# Copy_of_pilpal_final.net
KiCad netlist of a schematic drawn in Altium Designer
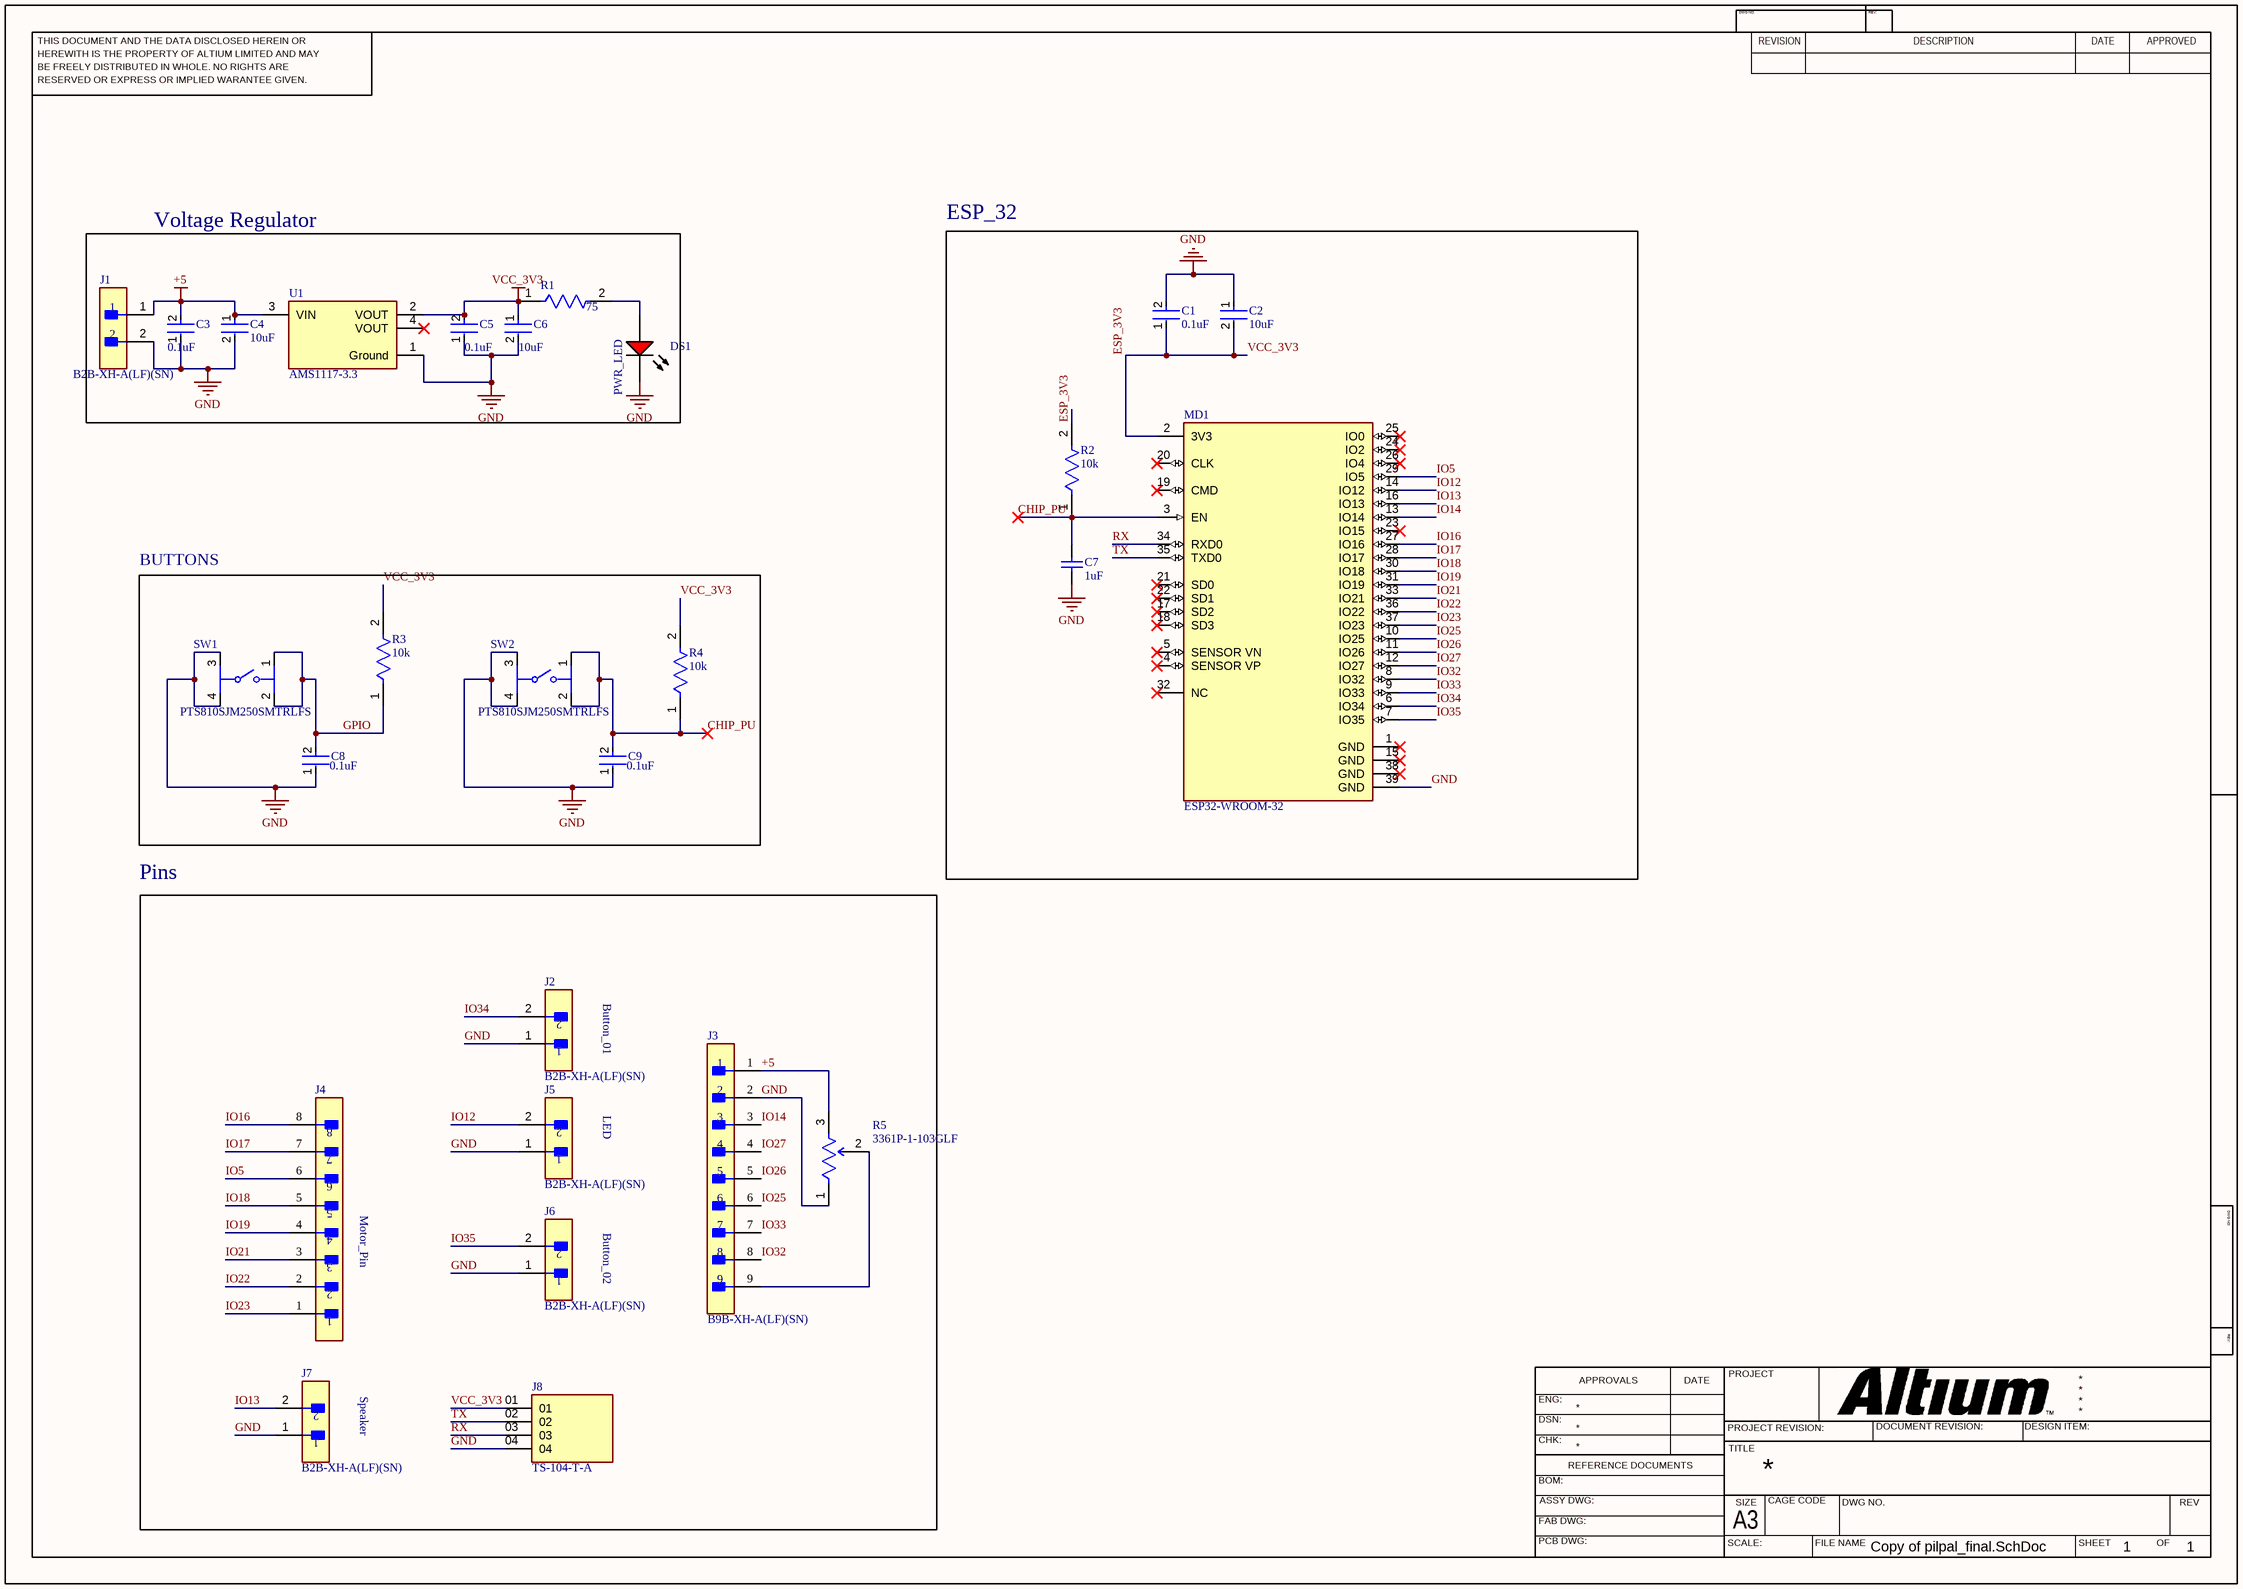
[diagram p0: Copy of pilpal_final.SchDoc]

(export (version "E")
  (design (tool "Eeschema 10.0.6"))
  (components
    (comp (ref "C1")
      (value "0.1uF")
      (footprint "FP-GRM15-MFG")
      (description "CAP CER 0.1UF 16V X7R 0402")
      (fields (field (name "MANUFACTURER PART NUMBER") "GRM155R71C104KA88D") (field (name "TOLERANCE") "10%"))
      (libsource (lib "Altium Content Vault") (part "236180d848d6139a670b325ea6854c9"))
    )
    (comp (ref "C2")
      (value "10uF")
      (footprint "FP-GRM188-0_1-e0_2_0_55-IPC_A")
      (description "Chip Multilayer Ceramic Capacitors for General Purpose, 0603, 10uF, X5R, 15%, 20%, 6.3V")
      (fields (field (name "VOLTAGE") "6.3V") (field (name "TOLERANCE") "20%"))
      (libsource (lib "Altium Content Vault") (part "02cd4be3c70576c341d710602a673aa"))
    )
    (comp (ref "C3")
      (value "0.1uF")
      (footprint "FP-GRM15-MFG")
      (description "CAP CER 0.1UF 16V X7R 0402")
      (fields (field (name "MANUFACTURER PART NUMBER") "GRM155R71C104KA88D") (field (name "TOLERANCE") "10%"))
      (libsource (lib "Altium Content Vault") (part "236180d848d6139a670b325ea6854c9"))
    )
    (comp (ref "C4")
      (value "10uF")
      (footprint "FP-GRM188-0_1-e0_2_0_55-IPC_A")
      (description "Chip Multilayer Ceramic Capacitors for General Purpose, 0603, 10uF, X5R, 15%, 20%, 6.3V")
      (fields (field (name "VOLTAGE") "6.3V") (field (name "TOLERANCE") "20%"))
      (libsource (lib "Altium Content Vault") (part "02cd4be3c70576c341d710602a673aa"))
    )
    (comp (ref "C5")
      (value "0.1uF")
      (footprint "FP-GRM15-MFG")
      (description "CAP CER 0.1UF 16V X7R 0402")
      (fields (field (name "MANUFACTURER PART NUMBER") "GRM155R71C104KA88D") (field (name "TOLERANCE") "10%"))
      (libsource (lib "Altium Content Vault") (part "236180d848d6139a670b325ea6854c9"))
    )
    (comp (ref "C6")
      (value "10uF")
      (footprint "FP-GRM188-0_1-e0_2_0_55-IPC_A")
      (description "Chip Multilayer Ceramic Capacitors for General Purpose, 0603, 10uF, X5R, 15%, 20%, 6.3V")
      (fields (field (name "VOLTAGE") "6.3V") (field (name "TOLERANCE") "20%"))
      (libsource (lib "Altium Content Vault") (part "02cd4be3c70576c341d710602a673aa"))
    )
    (comp (ref "C7")
      (value "1uF")
      (footprint "CAPC2013X145X50ML20T25")
      (fields (field (name "PART NUMBER") "C0805C105K9PACTU") (field (name "MANUFACTURER") "Kemet"))
      (libsource (lib "Altium Content Vault") (part "CAP"))
    )
    (comp (ref "C8")
      (value "0.1uF")
      (footprint "FP-GRM15-MFG")
      (description "CAP CER 0.1UF 16V X7R 0402")
      (fields (field (name "MANUFACTURER PART NUMBER") "GRM155R71C104KA88D") (field (name "TOLERANCE") "10%"))
      (libsource (lib "Altium Content Vault") (part "236180d848d6139a670b325ea6854c9"))
    )
    (comp (ref "C9")
      (value "0.1uF")
      (footprint "FP-GRM15-MFG")
      (description "CAP CER 0.1UF 16V X7R 0402")
      (fields (field (name "MANUFACTURER PART NUMBER") "GRM155R71C104KA88D") (field (name "TOLERANCE") "10%"))
      (libsource (lib "Altium Content Vault") (part "236180d848d6139a670b325ea6854c9"))
    )
    (comp (ref "DS1")
      (value "PWR_LED")
      (footprint "AVAG-HSMX-C150_V")
      (description "LED Uni-Color Red, 65 mW, 25 mA, -40 to 85 degC, 2-Pin SMD, RoHS, Tape and Reel")
      (fields (field (name "MANUFACTURER") "Avago"))
      (libsource (lib "Altium Content Vault") (part "LED-RED-AK-2"))
    )
    (comp (ref "J1")
      (value "B2B-XH-A(LF)(SN)")
      (footprint "FP-B2B-XH-A_LF_SN-MFG")
      (description "CONN HEADER VERT 2POS 2.5MM")
      (libsource (lib "") (part "3bc925449376181038e59eaffc5286c_1"))
    )
    (comp (ref "J2")
      (value "B2B-XH-A(LF)(SN)")
      (footprint "FP-B2B-XH-A_LF_SN-MFG")
      (description "CONN HEADER VERT 2POS 2.5MM")
      (libsource (lib "Altium Content Vault") (part "3bc925449376181038e59eaffc5286c"))
    )
    (comp (ref "J3")
      (value "B9B-XH-A(LF)(SN)")
      (footprint "FP-B9B-XH-A_LF_SN-MFG")
      (description "CONN HEADER VERT 9POS 2.5MM")
      (libsource (lib "Altium Content Vault") (part "dac6df820644cf490af5575b4ac23d9"))
    )
    (comp (ref "J4")
      (value "B8B-XH-A(LF)(SN)")
      (footprint "FP-B8B-XH-A_LF_SN-MFG")
      (description "CONN HEADER VERT 8POS 2.5MM")
      (libsource (lib "Altium Content Vault") (part "99ec2b232beb5d2356d4d77f6a047f0"))
    )
    (comp (ref "J5")
      (value "B2B-XH-A(LF)(SN)")
      (footprint "FP-B2B-XH-A_LF_SN-MFG")
      (description "CONN HEADER VERT 2POS 2.5MM")
      (libsource (lib "Altium Content Vault") (part "3bc925449376181038e59eaffc5286c"))
    )
    (comp (ref "J6")
      (value "B2B-XH-A(LF)(SN)")
      (footprint "FP-B2B-XH-A_LF_SN-MFG")
      (description "CONN HEADER VERT 2POS 2.5MM")
      (libsource (lib "Altium Content Vault") (part "3bc925449376181038e59eaffc5286c"))
    )
    (comp (ref "J7")
      (value "B2B-XH-A(LF)(SN)")
      (footprint "FP-B2B-XH-A_LF_SN-MFG")
      (description "CONN HEADER VERT 2POS 2.5MM")
      (libsource (lib "Altium Content Vault") (part "3bc925449376181038e59eaffc5286c"))
    )
    (comp (ref "J8")
      (value "TS-104-T-A")
      (footprint "SAMTEC_TS-104-T-A")
      (description "TS - Samtec 2.54mm Single Row Machined Terminal Strip - Fast Stock")
      (fields (field (name "MF") "Samtec Inc."))
      (libsource (lib "TS-104-T-A") (part "TS-104-T-A"))
    )
    (comp (ref "MD1")
      (value "ESP32-WROOM-32")
      (footprint "FP-ESP32-WROOM-32-MFG")
      (description "RX TXRX MOD WIFI SURFACE MOUNT")
      (libsource (lib "Altium Content Vault") (part "ee866abf0b6c51247b7f5cdebf2f250"))
    )
    (comp (ref "R1")
      (value "75")
      (footprint "FP-RN731J-MFG")
      (description "Thin Film Resistors RN 0603 750Ω 0.1% 10ppm/°C")
      (fields (field (name "TOLERANCE") "0.1%") (field (name "MANUFACTURER") "TE Connectivity"))
      (libsource (lib "Altium Content Vault") (part "1029c3af85768c4190bb7ad29bc67b5"))
    )
    (comp (ref "R2")
      (value "10k")
      (footprint "FP-CRG0805-IPC_C")
      (description "RES SMD 10K OHM 1% 1/8W 0805")
      (fields (field (name "TOLERANCE") "1%"))
      (libsource (lib "Altium Content Vault") (part "1029c3af85768c4190bb7ad29bc67b5"))
    )
    (comp (ref "R3")
      (value "10k")
      (footprint "FP-CRG0805-IPC_C")
      (description "RES SMD 10K OHM 1% 1/8W 0805")
      (fields (field (name "TOLERANCE") "1%"))
      (libsource (lib "Altium Content Vault") (part "1029c3af85768c4190bb7ad29bc67b5"))
    )
    (comp (ref "R4")
      (value "10k")
      (footprint "FP-CRG0805-IPC_C")
      (description "RES SMD 10K OHM 1% 1/8W 0805")
      (fields (field (name "TOLERANCE") "1%"))
      (libsource (lib "Altium Content Vault") (part "1029c3af85768c4190bb7ad29bc67b5"))
    )
    (comp (ref "R5")
      (value "3361P-1-103GLF")
      (footprint "FP-3361P-MFG")
      (description "TRIMMER 10K OHM 0.5W GW TOP ADJ")
      (fields (field (name "TOLERANCE") "10%"))
      (libsource (lib "Altium Content Vault") (part "2dcfd2547301a7d3209a5e99acfd772"))
    )
    (comp (ref "SW1")
      (value "PTS810SJM250SMTRLFS")
      (footprint "FP-PTS810SJM250SMTRLFS-MFG")
      (description "SWITCH TACTILE SPST-NO 0.05A 16V")
      (libsource (lib "Altium Content Vault") (part "1adf0dd01260c80cf25a44bfd6b99ba"))
    )
    (comp (ref "SW2")
      (value "PTS810SJM250SMTRLFS")
      (footprint "FP-PTS810SJM250SMTRLFS-MFG")
      (description "SWITCH TACTILE SPST-NO 0.05A 16V")
      (libsource (lib "Altium Content Vault") (part "1adf0dd01260c80cf25a44bfd6b99ba"))
    )
    (comp (ref "U1")
      (value "AMS1117-3.3")
      (footprint "FP-AMS1117-IPC_C")
      (description "LDO Voltage Regulators 1A, 3.3V")
      (fields
        (field (name "OCTOPART") "https://octopart.com/ams1117-3.3-advanced+monolithic+systems-25899300")
        (field (name "MANUFACTURER") "Advanced Monolithic Systems")
      )
      (libsource (lib "Altium Content Vault") (part "8bdbb5f8e77002000e30dd2845d0354"))
    )
  )
  (nets
    (net (code "1") (name "+5") (class "Default")
      (node (ref "C3") (pin "2") (pinfunction "2_2") (pintype "passive"))
      (node (ref "C4") (pin "1") (pinfunction "1_1") (pintype "passive"))
      (node (ref "J1") (pin "1") (pinfunction "1_1") (pintype "passive"))
      (node (ref "J3") (pin "1") (pinfunction "1_1") (pintype "passive"))
      (node (ref "R5") (pin "3") (pinfunction "CW_3") (pintype "passive"))
      (node (ref "U1") (pin "3") (pinfunction "VIN_3") (pintype "power_in"))
    )
    (net (code "2") (name "/CHIP_PU") (class "Default")
      (node (ref "C7") (pin "2") (pinfunction "2_2") (pintype "passive"))
      (node (ref "C9") (pin "2") (pinfunction "2_2") (pintype "passive"))
      (node (ref "MD1") (pin "3") (pinfunction "EN_3") (pintype "input"))
      (node (ref "R2") (pin "1") (pinfunction "1_1") (pintype "passive"))
      (node (ref "R4") (pin "1") (pinfunction "1_1") (pintype "passive"))
      (node (ref "SW2") (pin "1") (pinfunction "1_1") (pintype "passive"))
      (node (ref "SW2") (pin "2") (pinfunction "2_2") (pintype "passive"))
    )
    (net (code "3") (name "/GPIO") (class "Default")
      (node (ref "C8") (pin "2") (pinfunction "2_2") (pintype "passive"))
      (node (ref "R3") (pin "1") (pinfunction "1_1") (pintype "passive"))
      (node (ref "SW1") (pin "1") (pinfunction "1_1") (pintype "passive"))
      (node (ref "SW1") (pin "2") (pinfunction "2_2") (pintype "passive"))
    )
    (net (code "4") (name "/IO5") (class "Default")
      (node (ref "J4") (pin "6") (pinfunction "6_6") (pintype "passive"))
      (node (ref "MD1") (pin "29") (pinfunction "IO5_29") (pintype "bidirectional"))
    )
    (net (code "5") (name "/IO12") (class "Default")
      (node (ref "J5") (pin "2") (pinfunction "2_2") (pintype "passive"))
      (node (ref "MD1") (pin "14") (pinfunction "IO12_14") (pintype "bidirectional"))
    )
    (net (code "6") (name "/IO13") (class "Default")
      (node (ref "J7") (pin "2") (pinfunction "2_2") (pintype "passive"))
      (node (ref "MD1") (pin "16") (pinfunction "IO13_16") (pintype "bidirectional"))
    )
    (net (code "7") (name "/IO14") (class "Default")
      (node (ref "J3") (pin "3") (pinfunction "3_3") (pintype "passive"))
      (node (ref "MD1") (pin "13") (pinfunction "IO14_13") (pintype "bidirectional"))
    )
    (net (code "8") (name "/IO16") (class "Default")
      (node (ref "J4") (pin "8") (pinfunction "8_8") (pintype "passive"))
      (node (ref "MD1") (pin "27") (pinfunction "IO16_27") (pintype "bidirectional"))
    )
    (net (code "9") (name "/IO17") (class "Default")
      (node (ref "J4") (pin "7") (pinfunction "7_7") (pintype "passive"))
      (node (ref "MD1") (pin "28") (pinfunction "IO17_28") (pintype "bidirectional"))
    )
    (net (code "10") (name "/IO18") (class "Default")
      (node (ref "J4") (pin "5") (pinfunction "5_5") (pintype "passive"))
      (node (ref "MD1") (pin "30") (pinfunction "IO18_30") (pintype "bidirectional"))
    )
    (net (code "11") (name "/IO19") (class "Default")
      (node (ref "J4") (pin "4") (pinfunction "4_4") (pintype "passive"))
      (node (ref "MD1") (pin "31") (pinfunction "IO19_31") (pintype "bidirectional"))
    )
    (net (code "12") (name "/IO21") (class "Default")
      (node (ref "J4") (pin "3") (pinfunction "3_3") (pintype "passive"))
      (node (ref "MD1") (pin "33") (pinfunction "IO21_33") (pintype "bidirectional"))
    )
    (net (code "13") (name "/IO22") (class "Default")
      (node (ref "J4") (pin "2") (pinfunction "2_2") (pintype "passive"))
      (node (ref "MD1") (pin "36") (pinfunction "IO22_36") (pintype "bidirectional"))
    )
    (net (code "14") (name "/IO23") (class "Default")
      (node (ref "J4") (pin "1") (pinfunction "1_1") (pintype "passive"))
      (node (ref "MD1") (pin "37") (pinfunction "IO23_37") (pintype "bidirectional"))
    )
    (net (code "15") (name "/IO25") (class "Default")
      (node (ref "J3") (pin "6") (pinfunction "6_6") (pintype "passive"))
      (node (ref "MD1") (pin "10") (pinfunction "IO25_10") (pintype "bidirectional"))
    )
    (net (code "16") (name "/IO26") (class "Default")
      (node (ref "J3") (pin "5") (pinfunction "5_5") (pintype "passive"))
      (node (ref "MD1") (pin "11") (pinfunction "IO26_11") (pintype "bidirectional"))
    )
    (net (code "17") (name "/IO27") (class "Default")
      (node (ref "J3") (pin "4") (pinfunction "4_4") (pintype "passive"))
      (node (ref "MD1") (pin "12") (pinfunction "IO27_12") (pintype "bidirectional"))
    )
    (net (code "18") (name "/IO32") (class "Default")
      (node (ref "J3") (pin "8") (pinfunction "8_8") (pintype "passive"))
      (node (ref "MD1") (pin "8") (pinfunction "IO32_8") (pintype "bidirectional"))
    )
    (net (code "19") (name "/IO33") (class "Default")
      (node (ref "J3") (pin "7") (pinfunction "7_7") (pintype "passive"))
      (node (ref "MD1") (pin "9") (pinfunction "IO33_9") (pintype "bidirectional"))
    )
    (net (code "20") (name "/IO34") (class "Default")
      (node (ref "J2") (pin "2") (pinfunction "2_2") (pintype "passive"))
      (node (ref "MD1") (pin "6") (pinfunction "IO34_6") (pintype "bidirectional"))
    )
    (net (code "21") (name "/IO35") (class "Default")
      (node (ref "J6") (pin "2") (pinfunction "2_2") (pintype "passive"))
      (node (ref "MD1") (pin "7") (pinfunction "IO35_7") (pintype "bidirectional"))
    )
    (net (code "22") (name "/RX") (class "Default")
      (node (ref "J8") (pin "03") (pinfunction "03_03") (pintype "passive"))
      (node (ref "MD1") (pin "34") (pinfunction "RXD0_34") (pintype "bidirectional"))
    )
    (net (code "23") (name "/TX") (class "Default")
      (node (ref "J8") (pin "02") (pinfunction "02_02") (pintype "passive"))
      (node (ref "MD1") (pin "35") (pinfunction "TXD0_35") (pintype "bidirectional"))
    )
    (net (code "24") (name "GND") (class "Default")
      (node (ref "C1") (pin "2") (pinfunction "2_2") (pintype "passive"))
      (node (ref "C2") (pin "1") (pinfunction "1_1") (pintype "passive"))
      (node (ref "C3") (pin "1") (pinfunction "1_1") (pintype "passive"))
      (node (ref "C4") (pin "2") (pinfunction "2_2") (pintype "passive"))
      (node (ref "C5") (pin "1") (pinfunction "1_1") (pintype "passive"))
      (node (ref "C6") (pin "2") (pinfunction "2_2") (pintype "passive"))
      (node (ref "C7") (pin "1") (pinfunction "1_1") (pintype "passive"))
      (node (ref "C8") (pin "1") (pinfunction "1_1") (pintype "passive"))
      (node (ref "C9") (pin "1") (pinfunction "1_1") (pintype "passive"))
      (node (ref "DS1") (pin "2") (pinfunction "K_2") (pintype "passive"))
      (node (ref "J1") (pin "2") (pinfunction "2_2") (pintype "passive"))
      (node (ref "J2") (pin "1") (pinfunction "1_1") (pintype "passive"))
      (node (ref "J3") (pin "2") (pinfunction "2_2") (pintype "passive"))
      (node (ref "J5") (pin "1") (pinfunction "1_1") (pintype "passive"))
      (node (ref "J6") (pin "1") (pinfunction "1_1") (pintype "passive"))
      (node (ref "J7") (pin "1") (pinfunction "1_1") (pintype "passive"))
      (node (ref "J8") (pin "04") (pinfunction "04_04") (pintype "passive"))
      (node (ref "MD1") (pin "39") (pinfunction "GND_39") (pintype "power_in"))
      (node (ref "R5") (pin "1") (pinfunction "CCW_1") (pintype "passive"))
      (node (ref "SW1") (pin "3") (pinfunction "3_3") (pintype "passive"))
      (node (ref "SW1") (pin "4") (pinfunction "4_4") (pintype "passive"))
      (node (ref "SW2") (pin "3") (pinfunction "3_3") (pintype "passive"))
      (node (ref "SW2") (pin "4") (pinfunction "4_4") (pintype "passive"))
      (node (ref "U1") (pin "1") (pinfunction "Ground_1") (pintype "power_in"))
    )
    (net (code "25") (name "Net-(DS1-A)") (class "Default")
      (node (ref "DS1") (pin "1") (pinfunction "A_1") (pintype "passive"))
      (node (ref "R1") (pin "2") (pinfunction "2_2") (pintype "passive"))
    )
    (net (code "26") (name "Net-(R5-WIPER)") (class "Default")
      (node (ref "J3") (pin "9") (pinfunction "9_9") (pintype "passive"))
      (node (ref "R5") (pin "2") (pinfunction "WIPER_2") (pintype "passive"))
    )
    (net (code "27") (name "VCC_3V3") (class "Default")
      (node (ref "C1") (pin "1") (pinfunction "1_1") (pintype "passive"))
      (node (ref "C2") (pin "2") (pinfunction "2_2") (pintype "passive"))
      (node (ref "C5") (pin "2") (pinfunction "2_2") (pintype "passive"))
      (node (ref "C6") (pin "1") (pinfunction "1_1") (pintype "passive"))
      (node (ref "J8") (pin "01") (pinfunction "01_01") (pintype "passive"))
      (node (ref "MD1") (pin "2") (pinfunction "3V3_2") (pintype "power_in"))
      (node (ref "R1") (pin "1") (pinfunction "1_1") (pintype "passive"))
      (node (ref "R2") (pin "2") (pinfunction "2_2") (pintype "passive"))
      (node (ref "R3") (pin "2") (pinfunction "2_2") (pintype "passive"))
      (node (ref "R4") (pin "2") (pinfunction "2_2") (pintype "passive"))
      (node (ref "U1") (pin "2") (pinfunction "VOUT_2") (pintype "passive"))
    )
    (net (code "28") (name "unconnected-(MD1-CLK-Pad20)") (class "Default")
      (node (ref "MD1") (pin "20") (pinfunction "CLK_20") (pintype "bidirectional+no_connect"))
    )
    (net (code "29") (name "unconnected-(MD1-CMD-Pad19)") (class "Default")
      (node (ref "MD1") (pin "19") (pinfunction "CMD_19") (pintype "bidirectional+no_connect"))
    )
    (net (code "30") (name "unconnected-(MD1-GND-Pad1)") (class "Default")
      (node (ref "MD1") (pin "1") (pinfunction "GND_1") (pintype "power_in+no_connect"))
    )
    (net (code "31") (name "unconnected-(MD1-GND-Pad15)") (class "Default")
      (node (ref "MD1") (pin "15") (pinfunction "GND_15") (pintype "power_in+no_connect"))
    )
    (net (code "32") (name "unconnected-(MD1-GND-Pad38)") (class "Default")
      (node (ref "MD1") (pin "38") (pinfunction "GND_38") (pintype "power_in+no_connect"))
    )
    (net (code "33") (name "unconnected-(MD1-IO0-Pad25)") (class "Default")
      (node (ref "MD1") (pin "25") (pinfunction "IO0_25") (pintype "bidirectional+no_connect"))
    )
    (net (code "34") (name "unconnected-(MD1-IO2-Pad24)") (class "Default")
      (node (ref "MD1") (pin "24") (pinfunction "IO2_24") (pintype "bidirectional+no_connect"))
    )
    (net (code "35") (name "unconnected-(MD1-IO4-Pad26)") (class "Default")
      (node (ref "MD1") (pin "26") (pinfunction "IO4_26") (pintype "bidirectional+no_connect"))
    )
    (net (code "36") (name "unconnected-(MD1-IO15-Pad23)") (class "Default")
      (node (ref "MD1") (pin "23") (pinfunction "IO15_23") (pintype "bidirectional+no_connect"))
    )
    (net (code "37") (name "unconnected-(MD1-NC-Pad32)") (class "Default")
      (node (ref "MD1") (pin "32") (pinfunction "NC_32") (pintype "passive+no_connect"))
    )
    (net (code "38") (name "unconnected-(MD1-SD0-Pad21)") (class "Default")
      (node (ref "MD1") (pin "21") (pinfunction "SD0_21") (pintype "bidirectional+no_connect"))
    )
    (net (code "39") (name "unconnected-(MD1-SD1-Pad22)") (class "Default")
      (node (ref "MD1") (pin "22") (pinfunction "SD1_22") (pintype "bidirectional+no_connect"))
    )
    (net (code "40") (name "unconnected-(MD1-SD2-Pad17)") (class "Default")
      (node (ref "MD1") (pin "17") (pinfunction "SD2_17") (pintype "bidirectional+no_connect"))
    )
    (net (code "41") (name "unconnected-(MD1-SD3-Pad18)") (class "Default")
      (node (ref "MD1") (pin "18") (pinfunction "SD3_18") (pintype "bidirectional+no_connect"))
    )
    (net (code "42") (name "unconnected-(MD1-SENSOR_VN-Pad5)") (class "Default")
      (node (ref "MD1") (pin "5") (pinfunction "SENSOR_VN_5") (pintype "bidirectional+no_connect"))
    )
    (net (code "43") (name "unconnected-(MD1-SENSOR_VP-Pad4)") (class "Default")
      (node (ref "MD1") (pin "4") (pinfunction "SENSOR_VP_4") (pintype "bidirectional+no_connect"))
    )
    (net (code "44") (name "unconnected-(U1-VOUT-Pad4)") (class "Default")
      (node (ref "U1") (pin "4") (pinfunction "VOUT_4") (pintype "passive+no_connect"))
    )
  )
)
